# RedesignVaractorTline144Mhz.net
KiCad netlist of a schematic drawn in Altium Designer
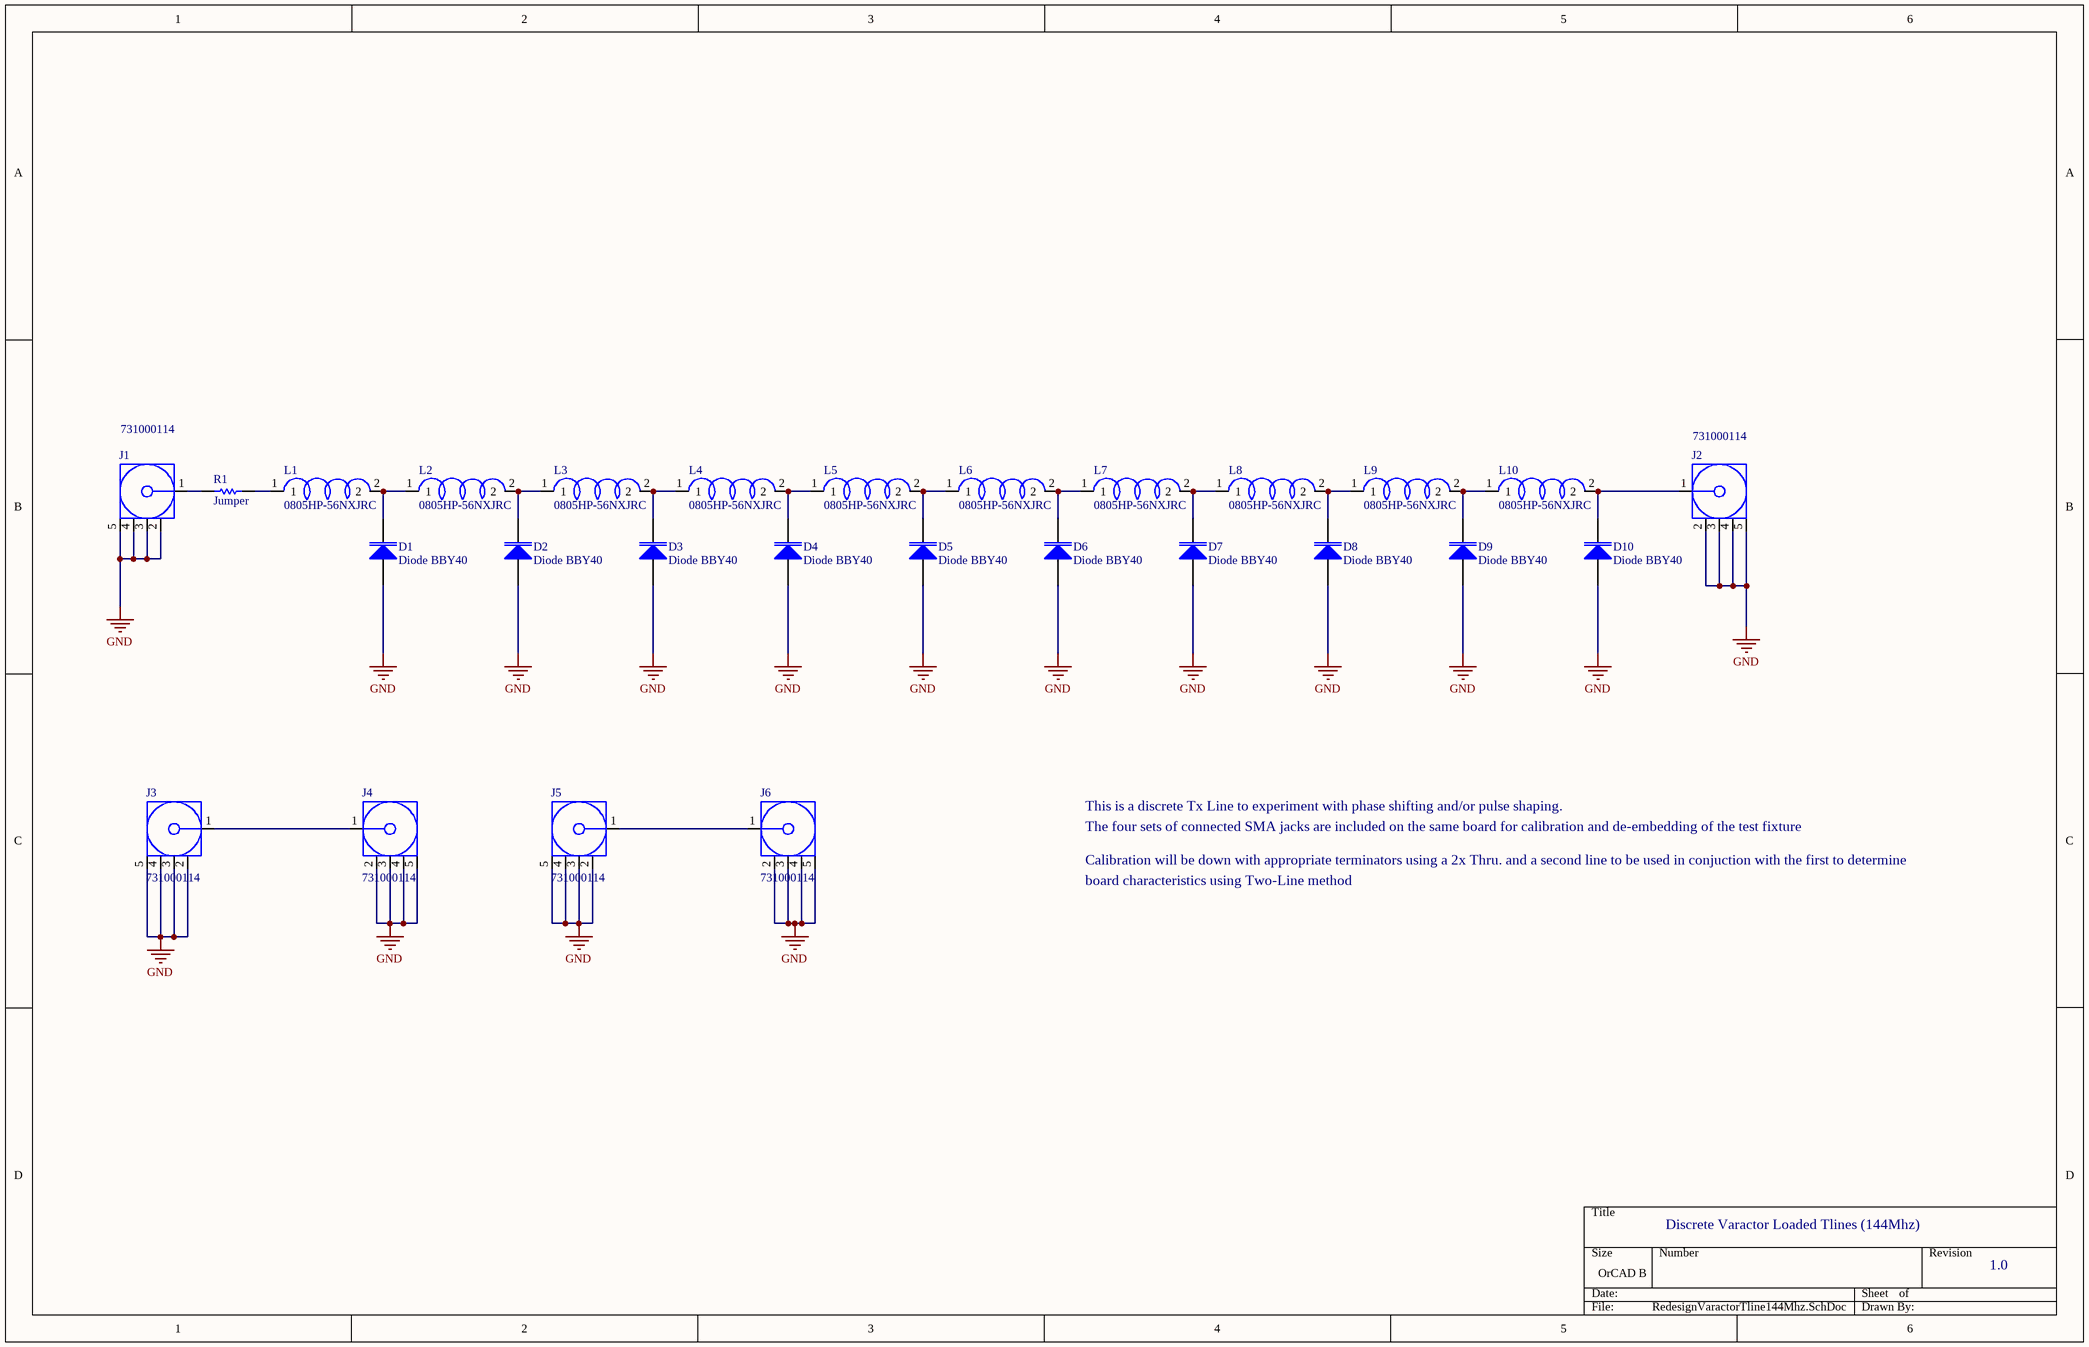
[diagram p0: RedesignVaractorTline144Mhz.SchDoc]

(export (version "E")
  (design (tool "Eeschema 10.0.6"))
  (components
    (comp (ref "D1")
      (value "Diode BBY40")
      (footprint "SOT23_N")
      (description "SOT23 Silicon Planar Variable Capacitance Diode")
      (fields (field (name "PUBLISHER") "Altium Limited"))
      (libsource (lib "Miscellaneous Devices") (part "Diode BBY40"))
    )
    (comp (ref "D2")
      (value "Diode BBY40")
      (footprint "SOT23_N")
      (description "SOT23 Silicon Planar Variable Capacitance Diode")
      (fields (field (name "PUBLISHER") "Altium Limited"))
      (libsource (lib "Miscellaneous Devices") (part "Diode BBY40"))
    )
    (comp (ref "D3")
      (value "Diode BBY40")
      (footprint "SOT23_N")
      (description "SOT23 Silicon Planar Variable Capacitance Diode")
      (fields (field (name "PUBLISHER") "Altium Limited"))
      (libsource (lib "Miscellaneous Devices") (part "Diode BBY40"))
    )
    (comp (ref "D4")
      (value "Diode BBY40")
      (footprint "SOT23_N")
      (description "SOT23 Silicon Planar Variable Capacitance Diode")
      (fields (field (name "PUBLISHER") "Altium Limited"))
      (libsource (lib "Miscellaneous Devices") (part "Diode BBY40"))
    )
    (comp (ref "D5")
      (value "Diode BBY40")
      (footprint "SOT23_N")
      (description "SOT23 Silicon Planar Variable Capacitance Diode")
      (fields (field (name "PUBLISHER") "Altium Limited"))
      (libsource (lib "Miscellaneous Devices") (part "Diode BBY40"))
    )
    (comp (ref "D6")
      (value "Diode BBY40")
      (footprint "SOT23_N")
      (description "SOT23 Silicon Planar Variable Capacitance Diode")
      (fields (field (name "PUBLISHER") "Altium Limited"))
      (libsource (lib "Miscellaneous Devices") (part "Diode BBY40"))
    )
    (comp (ref "D7")
      (value "Diode BBY40")
      (footprint "SOT23_N")
      (description "SOT23 Silicon Planar Variable Capacitance Diode")
      (fields (field (name "PUBLISHER") "Altium Limited"))
      (libsource (lib "Miscellaneous Devices") (part "Diode BBY40"))
    )
    (comp (ref "D8")
      (value "Diode BBY40")
      (footprint "SOT23_N")
      (description "SOT23 Silicon Planar Variable Capacitance Diode")
      (fields (field (name "PUBLISHER") "Altium Limited"))
      (libsource (lib "Miscellaneous Devices") (part "Diode BBY40"))
    )
    (comp (ref "D9")
      (value "Diode BBY40")
      (footprint "SOT23_N")
      (description "SOT23 Silicon Planar Variable Capacitance Diode")
      (fields (field (name "PUBLISHER") "Altium Limited"))
      (libsource (lib "Miscellaneous Devices") (part "Diode BBY40"))
    )
    (comp (ref "D10")
      (value "Diode BBY40")
      (footprint "SOT23_N")
      (description "SOT23 Silicon Planar Variable Capacitance Diode")
      (fields (field (name "PUBLISHER") "Altium Limited"))
      (libsource (lib "Miscellaneous Devices") (part "Diode BBY40"))
    )
    (comp (ref "J1")
      (value "731000114")
      (footprint "MOLX-731000114_V")
      (description "SMA Right-Angle PCB Jack Receptacle, Brass Body, Gold Plated, 50 Ohm, 5-Pin THD, RoHS, Tray")
      (fields (field (name "MANUFACTURER") "Molex"))
      (libsource (lib "Altium Content Vault") (part "CN-S-4F-RF5"))
    )
    (comp (ref "J2")
      (value "731000114")
      (footprint "MOLX-731000114_V")
      (description "SMA Right-Angle PCB Jack Receptacle, Brass Body, Gold Plated, 50 Ohm, 5-Pin THD, RoHS, Tray")
      (fields (field (name "MANUFACTURER") "Molex"))
      (libsource (lib "Altium Content Vault") (part "CN-S-4F-RF5"))
    )
    (comp (ref "J3")
      (value "731000114")
      (footprint "MOLX-731000114_V")
      (description "SMA Right-Angle PCB Jack Receptacle, Brass Body, Gold Plated, 50 Ohm, 5-Pin THD, RoHS, Tray")
      (fields (field (name "MANUFACTURER") "Molex"))
      (libsource (lib "Altium Content Vault") (part "CN-S-4F-RF5"))
    )
    (comp (ref "J4")
      (value "731000114")
      (footprint "MOLX-731000114_V")
      (description "SMA Right-Angle PCB Jack Receptacle, Brass Body, Gold Plated, 50 Ohm, 5-Pin THD, RoHS, Tray")
      (fields (field (name "MANUFACTURER") "Molex"))
      (libsource (lib "Altium Content Vault") (part "CN-S-4F-RF5"))
    )
    (comp (ref "J5")
      (value "731000114")
      (footprint "MOLX-731000114_V")
      (description "SMA Right-Angle PCB Jack Receptacle, Brass Body, Gold Plated, 50 Ohm, 5-Pin THD, RoHS, Tray")
      (fields (field (name "MANUFACTURER") "Molex"))
      (libsource (lib "Altium Content Vault") (part "CN-S-4F-RF5"))
    )
    (comp (ref "J6")
      (value "731000114")
      (footprint "MOLX-731000114_V")
      (description "SMA Right-Angle PCB Jack Receptacle, Brass Body, Gold Plated, 50 Ohm, 5-Pin THD, RoHS, Tray")
      (fields (field (name "MANUFACTURER") "Molex"))
      (libsource (lib "Altium Content Vault") (part "CN-S-4F-RF5"))
    )
    (comp (ref "L1")
      (value "0805HP-56NXJRC")
      (footprint "0805HQ SERIES")
      (description "0805HP-56NXJRC Coilcraft Variable Inductor")
      (fields (field (name "MANUFACTURER") "Coilcraft"))
      (libsource (lib "114MhzDiscreteTxline") (part "0805HP-56NXJRC"))
    )
    (comp (ref "L2")
      (value "0805HP-56NXJRC")
      (footprint "0805HQ SERIES")
      (description "0805HP-56NXJRC Coilcraft Variable Inductor")
      (fields (field (name "MANUFACTURER") "Coilcraft"))
      (libsource (lib "114MhzDiscreteTxline") (part "0805HP-56NXJRC"))
    )
    (comp (ref "L3")
      (value "0805HP-56NXJRC")
      (footprint "0805HQ SERIES")
      (description "0805HP-56NXJRC Coilcraft Variable Inductor")
      (fields (field (name "MANUFACTURER") "Coilcraft"))
      (libsource (lib "114MhzDiscreteTxline") (part "0805HP-56NXJRC"))
    )
    (comp (ref "L4")
      (value "0805HP-56NXJRC")
      (footprint "0805HQ SERIES")
      (description "0805HP-56NXJRC Coilcraft Variable Inductor")
      (fields (field (name "MANUFACTURER") "Coilcraft"))
      (libsource (lib "114MhzDiscreteTxline") (part "0805HP-56NXJRC"))
    )
    (comp (ref "L5")
      (value "0805HP-56NXJRC")
      (footprint "0805HQ SERIES")
      (description "0805HP-56NXJRC Coilcraft Variable Inductor")
      (fields (field (name "MANUFACTURER") "Coilcraft"))
      (libsource (lib "114MhzDiscreteTxline") (part "0805HP-56NXJRC"))
    )
    (comp (ref "L6")
      (value "0805HP-56NXJRC")
      (footprint "0805HQ SERIES")
      (description "0805HP-56NXJRC Coilcraft Variable Inductor")
      (fields (field (name "MANUFACTURER") "Coilcraft"))
      (libsource (lib "114MhzDiscreteTxline") (part "0805HP-56NXJRC"))
    )
    (comp (ref "L7")
      (value "0805HP-56NXJRC")
      (footprint "0805HQ SERIES")
      (description "0805HP-56NXJRC Coilcraft Variable Inductor")
      (fields (field (name "MANUFACTURER") "Coilcraft"))
      (libsource (lib "114MhzDiscreteTxline") (part "0805HP-56NXJRC"))
    )
    (comp (ref "L8")
      (value "0805HP-56NXJRC")
      (footprint "0805HQ SERIES")
      (description "0805HP-56NXJRC Coilcraft Variable Inductor")
      (fields (field (name "MANUFACTURER") "Coilcraft"))
      (libsource (lib "114MhzDiscreteTxline") (part "0805HP-56NXJRC"))
    )
    (comp (ref "L9")
      (value "0805HP-56NXJRC")
      (footprint "0805HQ SERIES")
      (description "0805HP-56NXJRC Coilcraft Variable Inductor")
      (fields (field (name "MANUFACTURER") "Coilcraft"))
      (libsource (lib "114MhzDiscreteTxline") (part "0805HP-56NXJRC"))
    )
    (comp (ref "L10")
      (value "0805HP-56NXJRC")
      (footprint "0805HQ SERIES")
      (description "0805HP-56NXJRC Coilcraft Variable Inductor")
      (fields (field (name "MANUFACTURER") "Coilcraft"))
      (libsource (lib "114MhzDiscreteTxline") (part "0805HP-56NXJRC"))
    )
    (comp (ref "R1")
      (value "Jumper")
      (footprint "RESC2013X70X40NL20T20")
      (description "Chip Resistor, 0 Ohm, +/- 1%, 0.125 W, -55 to 155 degC, 0805 (2012 Metric), RoHS, Tape and Reel")
      (fields (field (name "PARTNUMBER") "ERJ-6GEY0R00V") (field (name "TOLERANCE") "5%"))
      (libsource (lib "Altium Content Vault") (part "RES-2"))
    )
  )
  (nets
    (net (code "1") (name "GND") (class "Default")
      (node (ref "D1") (pin "3") (pinfunction "A_3") (pintype "passive"))
      (node (ref "D10") (pin "3") (pinfunction "A_3") (pintype "passive"))
      (node (ref "D2") (pin "3") (pinfunction "A_3") (pintype "passive"))
      (node (ref "D3") (pin "3") (pinfunction "A_3") (pintype "passive"))
      (node (ref "D4") (pin "3") (pinfunction "A_3") (pintype "passive"))
      (node (ref "D5") (pin "3") (pinfunction "A_3") (pintype "passive"))
      (node (ref "D6") (pin "3") (pinfunction "A_3") (pintype "passive"))
      (node (ref "D7") (pin "3") (pinfunction "A_3") (pintype "passive"))
      (node (ref "D8") (pin "3") (pinfunction "A_3") (pintype "passive"))
      (node (ref "D9") (pin "3") (pinfunction "A_3") (pintype "passive"))
      (node (ref "J1") (pin "2") (pinfunction "2_2") (pintype "passive"))
      (node (ref "J1") (pin "3") (pinfunction "3_3") (pintype "passive"))
      (node (ref "J1") (pin "4") (pinfunction "4_4") (pintype "passive"))
      (node (ref "J1") (pin "5") (pinfunction "5_5") (pintype "passive"))
      (node (ref "J2") (pin "2") (pinfunction "2_2") (pintype "passive"))
      (node (ref "J2") (pin "3") (pinfunction "3_3") (pintype "passive"))
      (node (ref "J2") (pin "4") (pinfunction "4_4") (pintype "passive"))
      (node (ref "J2") (pin "5") (pinfunction "5_5") (pintype "passive"))
      (node (ref "J3") (pin "2") (pinfunction "2_2") (pintype "passive"))
      (node (ref "J3") (pin "3") (pinfunction "3_3") (pintype "passive"))
      (node (ref "J3") (pin "4") (pinfunction "4_4") (pintype "passive"))
      (node (ref "J3") (pin "5") (pinfunction "5_5") (pintype "passive"))
      (node (ref "J4") (pin "2") (pinfunction "2_2") (pintype "passive"))
      (node (ref "J4") (pin "3") (pinfunction "3_3") (pintype "passive"))
      (node (ref "J4") (pin "4") (pinfunction "4_4") (pintype "passive"))
      (node (ref "J4") (pin "5") (pinfunction "5_5") (pintype "passive"))
      (node (ref "J5") (pin "2") (pinfunction "2_2") (pintype "passive"))
      (node (ref "J5") (pin "3") (pinfunction "3_3") (pintype "passive"))
      (node (ref "J5") (pin "4") (pinfunction "4_4") (pintype "passive"))
      (node (ref "J5") (pin "5") (pinfunction "5_5") (pintype "passive"))
      (node (ref "J6") (pin "2") (pinfunction "2_2") (pintype "passive"))
      (node (ref "J6") (pin "3") (pinfunction "3_3") (pintype "passive"))
      (node (ref "J6") (pin "4") (pinfunction "4_4") (pintype "passive"))
      (node (ref "J6") (pin "5") (pinfunction "5_5") (pintype "passive"))
    )
    (net (code "2") (name "Net-(D1-K)") (class "Default")
      (node (ref "D1") (pin "1") (pinfunction "K_1") (pintype "passive"))
      (node (ref "L1") (pin "2") (pinfunction "2_2") (pintype "passive"))
      (node (ref "L2") (pin "1") (pinfunction "1_1") (pintype "passive"))
    )
    (net (code "3") (name "Net-(D2-K)") (class "Default")
      (node (ref "D2") (pin "1") (pinfunction "K_1") (pintype "passive"))
      (node (ref "L2") (pin "2") (pinfunction "2_2") (pintype "passive"))
      (node (ref "L3") (pin "1") (pinfunction "1_1") (pintype "passive"))
    )
    (net (code "4") (name "Net-(D3-K)") (class "Default")
      (node (ref "D3") (pin "1") (pinfunction "K_1") (pintype "passive"))
      (node (ref "L3") (pin "2") (pinfunction "2_2") (pintype "passive"))
      (node (ref "L4") (pin "1") (pinfunction "1_1") (pintype "passive"))
    )
    (net (code "5") (name "Net-(D4-K)") (class "Default")
      (node (ref "D4") (pin "1") (pinfunction "K_1") (pintype "passive"))
      (node (ref "L4") (pin "2") (pinfunction "2_2") (pintype "passive"))
      (node (ref "L5") (pin "1") (pinfunction "1_1") (pintype "passive"))
    )
    (net (code "6") (name "Net-(D5-K)") (class "Default")
      (node (ref "D5") (pin "1") (pinfunction "K_1") (pintype "passive"))
      (node (ref "L5") (pin "2") (pinfunction "2_2") (pintype "passive"))
      (node (ref "L6") (pin "1") (pinfunction "1_1") (pintype "passive"))
    )
    (net (code "7") (name "Net-(D6-K)") (class "Default")
      (node (ref "D6") (pin "1") (pinfunction "K_1") (pintype "passive"))
      (node (ref "L6") (pin "2") (pinfunction "2_2") (pintype "passive"))
      (node (ref "L7") (pin "1") (pinfunction "1_1") (pintype "passive"))
    )
    (net (code "8") (name "Net-(D7-K)") (class "Default")
      (node (ref "D7") (pin "1") (pinfunction "K_1") (pintype "passive"))
      (node (ref "L7") (pin "2") (pinfunction "2_2") (pintype "passive"))
      (node (ref "L8") (pin "1") (pinfunction "1_1") (pintype "passive"))
    )
    (net (code "9") (name "Net-(D8-K)") (class "Default")
      (node (ref "D8") (pin "1") (pinfunction "K_1") (pintype "passive"))
      (node (ref "L8") (pin "2") (pinfunction "2_2") (pintype "passive"))
      (node (ref "L9") (pin "1") (pinfunction "1_1") (pintype "passive"))
    )
    (net (code "10") (name "Net-(D9-K)") (class "Default")
      (node (ref "D9") (pin "1") (pinfunction "K_1") (pintype "passive"))
      (node (ref "L10") (pin "1") (pinfunction "1_1") (pintype "passive"))
      (node (ref "L9") (pin "2") (pinfunction "2_2") (pintype "passive"))
    )
    (net (code "11") (name "Net-(D10-K)") (class "Default")
      (node (ref "D10") (pin "1") (pinfunction "K_1") (pintype "passive"))
      (node (ref "J2") (pin "1") (pinfunction "1_1") (pintype "passive"))
      (node (ref "L10") (pin "2") (pinfunction "2_2") (pintype "passive"))
    )
    (net (code "12") (name "Net-(J1-Pad1)") (class "Default")
      (node (ref "J1") (pin "1") (pinfunction "1_1") (pintype "passive"))
      (node (ref "R1") (pin "1") (pinfunction "1_1") (pintype "passive"))
    )
    (net (code "13") (name "Net-(J3-Pad1)") (class "Default")
      (node (ref "J3") (pin "1") (pinfunction "1_1") (pintype "passive"))
      (node (ref "J4") (pin "1") (pinfunction "1_1") (pintype "passive"))
    )
    (net (code "14") (name "Net-(J5-Pad1)") (class "Default")
      (node (ref "J5") (pin "1") (pinfunction "1_1") (pintype "passive"))
      (node (ref "J6") (pin "1") (pinfunction "1_1") (pintype "passive"))
    )
    (net (code "15") (name "Net-(L1-Pad1)") (class "Default")
      (node (ref "L1") (pin "1") (pinfunction "1_1") (pintype "passive"))
      (node (ref "R1") (pin "2") (pinfunction "2_2") (pintype "passive"))
    )
  )
)
